# Interface.net
KiCad netlist of a schematic drawn in Altium Designer
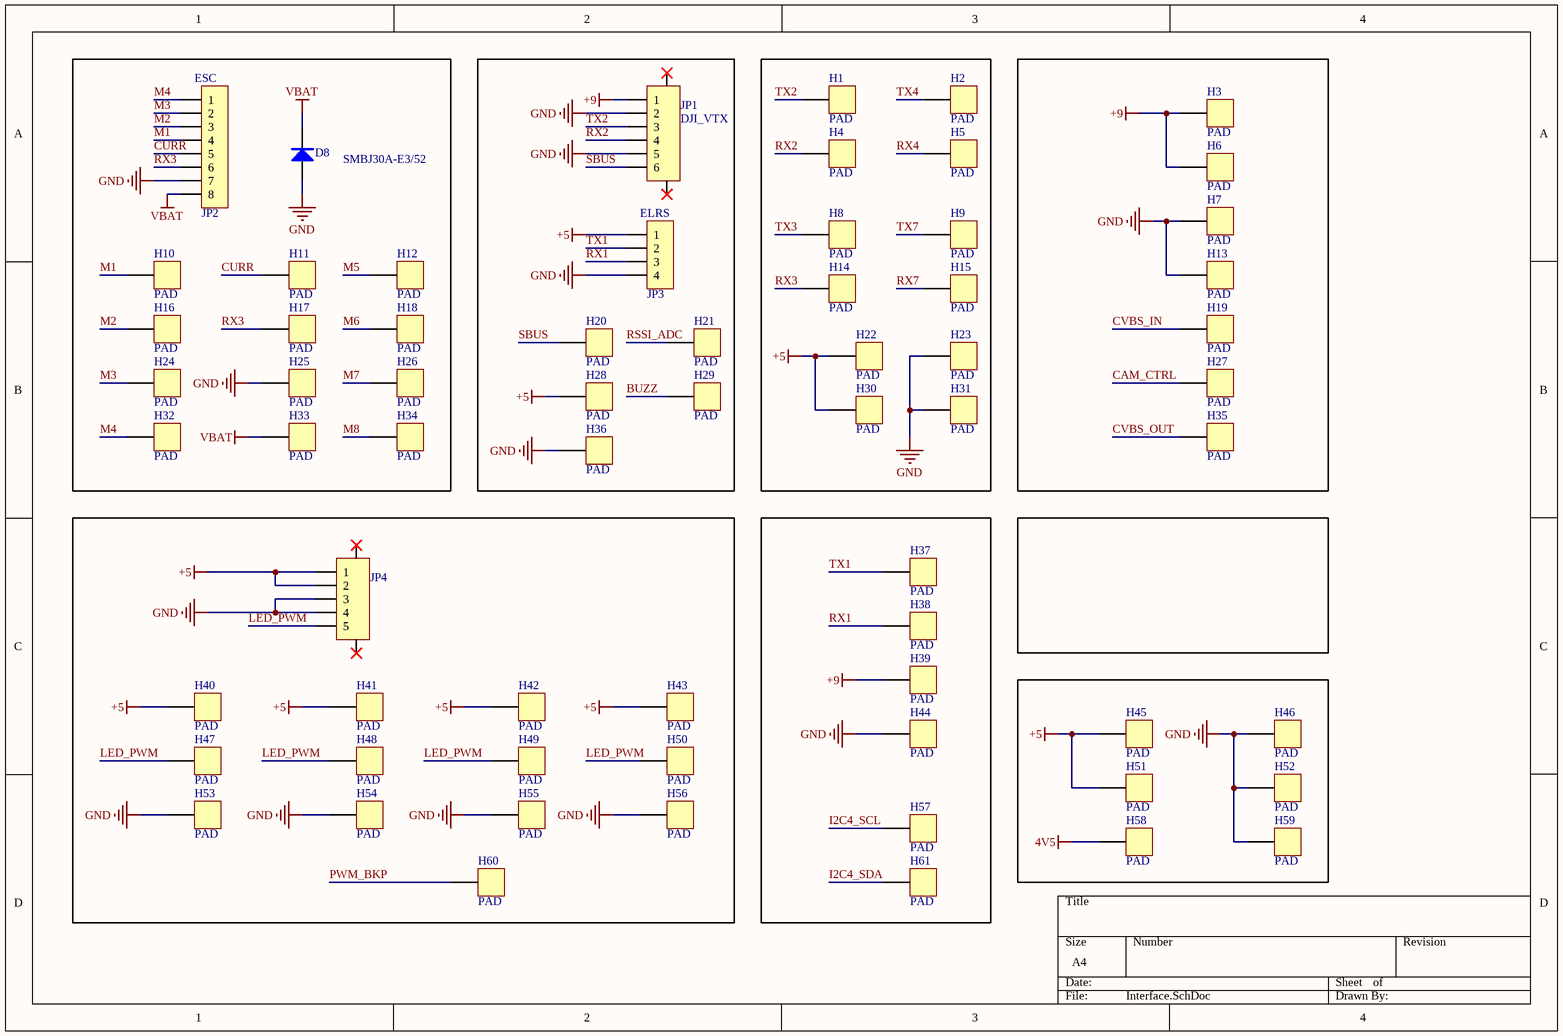
[diagram p0: Interface.SchDoc]

(export (version "E")
  (design (tool "Eeschema 10.0.6"))
  (components
    (comp (ref "D8")
      (value "SMBJ30A-E3/52")
      (footprint "SMB")
      (description "30V 600W 瞬态抑制二极管(TVS)")
      (libsource (lib "AxisQuad Components Lib") (part "SMBJ30A-E3/52"))
    )
    (comp (ref "H1")
      (value "PAD")
      (footprint "Pad 4")
      (description "Pads")
      (libsource (lib "Daedalus Components Lib") (part "PAD"))
    )
    (comp (ref "H2")
      (value "PAD")
      (footprint "Pad 4")
      (description "Pads")
      (libsource (lib "Daedalus Components Lib") (part "PAD"))
    )
    (comp (ref "H3")
      (value "PAD")
      (footprint "Pad 4")
      (description "Pads")
      (libsource (lib "Daedalus Components Lib") (part "PAD"))
    )
    (comp (ref "H4")
      (value "PAD")
      (footprint "Pad 4")
      (description "Pads")
      (libsource (lib "Daedalus Components Lib") (part "PAD"))
    )
    (comp (ref "H5")
      (value "PAD")
      (footprint "Pad 4")
      (description "Pads")
      (libsource (lib "Daedalus Components Lib") (part "PAD"))
    )
    (comp (ref "H6")
      (value "PAD")
      (footprint "Pad 4")
      (description "Pads")
      (libsource (lib "Daedalus Components Lib") (part "PAD"))
    )
    (comp (ref "H7")
      (value "PAD")
      (footprint "Pad 4")
      (description "Pads")
      (libsource (lib "Daedalus Components Lib") (part "PAD"))
    )
    (comp (ref "H8")
      (value "PAD")
      (footprint "Pad 4")
      (description "Pads")
      (libsource (lib "Daedalus Components Lib") (part "PAD"))
    )
    (comp (ref "H9")
      (value "PAD")
      (footprint "Pad 4")
      (description "Pads")
      (libsource (lib "Daedalus Components Lib") (part "PAD"))
    )
    (comp (ref "H10")
      (value "PAD")
      (footprint "Pad 4")
      (description "Pads")
      (libsource (lib "Daedalus Components Lib") (part "PAD"))
    )
    (comp (ref "H11")
      (value "PAD")
      (footprint "Pad 4")
      (description "Pads")
      (libsource (lib "Daedalus Components Lib") (part "PAD"))
    )
    (comp (ref "H12")
      (value "PAD")
      (footprint "Pad 4")
      (description "Pads")
      (libsource (lib "Daedalus Components Lib") (part "PAD"))
    )
    (comp (ref "H13")
      (value "PAD")
      (footprint "Pad 4")
      (description "Pads")
      (libsource (lib "Daedalus Components Lib") (part "PAD"))
    )
    (comp (ref "H14")
      (value "PAD")
      (footprint "Pad 4")
      (description "Pads")
      (libsource (lib "Daedalus Components Lib") (part "PAD"))
    )
    (comp (ref "H15")
      (value "PAD")
      (footprint "Pad 4")
      (description "Pads")
      (libsource (lib "Daedalus Components Lib") (part "PAD"))
    )
    (comp (ref "H16")
      (value "PAD")
      (footprint "Pad 4")
      (description "Pads")
      (libsource (lib "Daedalus Components Lib") (part "PAD"))
    )
    (comp (ref "H17")
      (value "PAD")
      (footprint "Pad 4")
      (description "Pads")
      (libsource (lib "Daedalus Components Lib") (part "PAD"))
    )
    (comp (ref "H18")
      (value "PAD")
      (footprint "Pad 4")
      (description "Pads")
      (libsource (lib "Daedalus Components Lib") (part "PAD"))
    )
    (comp (ref "H19")
      (value "PAD")
      (footprint "Pad 4")
      (description "Pads")
      (libsource (lib "Daedalus Components Lib") (part "PAD"))
    )
    (comp (ref "H20")
      (value "PAD")
      (footprint "Pad 4")
      (description "Pads")
      (libsource (lib "Daedalus Components Lib") (part "PAD"))
    )
    (comp (ref "H21")
      (value "PAD")
      (footprint "Pad 4")
      (description "Pads")
      (libsource (lib "Daedalus Components Lib") (part "PAD"))
    )
    (comp (ref "H22")
      (value "PAD")
      (footprint "Pad 4")
      (description "Pads")
      (libsource (lib "Daedalus Components Lib") (part "PAD"))
    )
    (comp (ref "H23")
      (value "PAD")
      (footprint "Pad 4")
      (description "Pads")
      (libsource (lib "Daedalus Components Lib") (part "PAD"))
    )
    (comp (ref "H24")
      (value "PAD")
      (footprint "Pad 4")
      (description "Pads")
      (libsource (lib "Daedalus Components Lib") (part "PAD"))
    )
    (comp (ref "H25")
      (value "PAD")
      (footprint "Pad 4")
      (description "Pads")
      (libsource (lib "Daedalus Components Lib") (part "PAD"))
    )
    (comp (ref "H26")
      (value "PAD")
      (footprint "Pad 4")
      (description "Pads")
      (libsource (lib "Daedalus Components Lib") (part "PAD"))
    )
    (comp (ref "H27")
      (value "PAD")
      (footprint "Pad 4")
      (description "Pads")
      (libsource (lib "Daedalus Components Lib") (part "PAD"))
    )
    (comp (ref "H28")
      (value "PAD")
      (footprint "Pad 4")
      (description "Pads")
      (libsource (lib "Daedalus Components Lib") (part "PAD"))
    )
    (comp (ref "H29")
      (value "PAD")
      (footprint "Pad 4")
      (description "Pads")
      (libsource (lib "Daedalus Components Lib") (part "PAD"))
    )
    (comp (ref "H30")
      (value "PAD")
      (footprint "Pad 4")
      (description "Pads")
      (libsource (lib "Daedalus Components Lib") (part "PAD"))
    )
    (comp (ref "H31")
      (value "PAD")
      (footprint "Pad 4")
      (description "Pads")
      (libsource (lib "Daedalus Components Lib") (part "PAD"))
    )
    (comp (ref "H32")
      (value "PAD")
      (footprint "Pad 4")
      (description "Pads")
      (libsource (lib "Daedalus Components Lib") (part "PAD"))
    )
    (comp (ref "H33")
      (value "PAD")
      (footprint "Pad 4")
      (description "Pads")
      (libsource (lib "Daedalus Components Lib") (part "PAD"))
    )
    (comp (ref "H34")
      (value "PAD")
      (footprint "Pad 4")
      (description "Pads")
      (libsource (lib "Daedalus Components Lib") (part "PAD"))
    )
    (comp (ref "H35")
      (value "PAD")
      (footprint "Pad 4")
      (description "Pads")
      (libsource (lib "Daedalus Components Lib") (part "PAD"))
    )
    (comp (ref "H36")
      (value "PAD")
      (footprint "Pad 4")
      (description "Pads")
      (libsource (lib "Daedalus Components Lib") (part "PAD"))
    )
    (comp (ref "H37")
      (value "PAD")
      (footprint "Pad 4")
      (description "Pads")
      (libsource (lib "Daedalus Components Lib") (part "PAD"))
    )
    (comp (ref "H38")
      (value "PAD")
      (footprint "Pad 4")
      (description "Pads")
      (libsource (lib "Daedalus Components Lib") (part "PAD"))
    )
    (comp (ref "H39")
      (value "PAD")
      (footprint "Pad 4")
      (description "Pads")
      (libsource (lib "Daedalus Components Lib") (part "PAD"))
    )
    (comp (ref "H40")
      (value "PAD")
      (footprint "Pad 2")
      (description "Pads")
      (libsource (lib "Daedalus Components Lib") (part "PAD"))
    )
    (comp (ref "H41")
      (value "PAD")
      (footprint "Pad 2")
      (description "Pads")
      (libsource (lib "Daedalus Components Lib") (part "PAD"))
    )
    (comp (ref "H42")
      (value "PAD")
      (footprint "Pad 2")
      (description "Pads")
      (libsource (lib "Daedalus Components Lib") (part "PAD"))
    )
    (comp (ref "H43")
      (value "PAD")
      (footprint "Pad 2")
      (description "Pads")
      (libsource (lib "Daedalus Components Lib") (part "PAD"))
    )
    (comp (ref "H44")
      (value "PAD")
      (footprint "Pad 4")
      (description "Pads")
      (libsource (lib "Daedalus Components Lib") (part "PAD"))
    )
    (comp (ref "H45")
      (value "PAD")
      (footprint "Pad 4")
      (description "Pads")
      (libsource (lib "Daedalus Components Lib") (part "PAD"))
    )
    (comp (ref "H46")
      (value "PAD")
      (footprint "Pad 4")
      (description "Pads")
      (libsource (lib "Daedalus Components Lib") (part "PAD"))
    )
    (comp (ref "H47")
      (value "PAD")
      (footprint "Pad 2")
      (description "Pads")
      (libsource (lib "Daedalus Components Lib") (part "PAD"))
    )
    (comp (ref "H48")
      (value "PAD")
      (footprint "Pad 2")
      (description "Pads")
      (libsource (lib "Daedalus Components Lib") (part "PAD"))
    )
    (comp (ref "H49")
      (value "PAD")
      (footprint "Pad 2")
      (description "Pads")
      (libsource (lib "Daedalus Components Lib") (part "PAD"))
    )
    (comp (ref "H50")
      (value "PAD")
      (footprint "Pad 2")
      (description "Pads")
      (libsource (lib "Daedalus Components Lib") (part "PAD"))
    )
    (comp (ref "H51")
      (value "PAD")
      (footprint "Pad 4")
      (description "Pads")
      (libsource (lib "Daedalus Components Lib") (part "PAD"))
    )
    (comp (ref "H52")
      (value "PAD")
      (footprint "Pad 4")
      (description "Pads")
      (libsource (lib "Daedalus Components Lib") (part "PAD"))
    )
    (comp (ref "H53")
      (value "PAD")
      (footprint "Pad 2")
      (description "Pads")
      (libsource (lib "Daedalus Components Lib") (part "PAD"))
    )
    (comp (ref "H54")
      (value "PAD")
      (footprint "Pad 2")
      (description "Pads")
      (libsource (lib "Daedalus Components Lib") (part "PAD"))
    )
    (comp (ref "H55")
      (value "PAD")
      (footprint "Pad 2")
      (description "Pads")
      (libsource (lib "Daedalus Components Lib") (part "PAD"))
    )
    (comp (ref "H56")
      (value "PAD")
      (footprint "Pad 2")
      (description "Pads")
      (libsource (lib "Daedalus Components Lib") (part "PAD"))
    )
    (comp (ref "H57")
      (value "PAD")
      (footprint "Pad 4")
      (description "Pads")
      (libsource (lib "Daedalus Components Lib") (part "PAD"))
    )
    (comp (ref "H58")
      (value "PAD")
      (footprint "Pad 2")
      (description "Pads")
      (libsource (lib "Daedalus Components Lib") (part "PAD"))
    )
    (comp (ref "H59")
      (value "PAD")
      (footprint "Pad 2")
      (description "Pads")
      (libsource (lib "Daedalus Components Lib") (part "PAD"))
    )
    (comp (ref "H60")
      (value "PAD")
      (footprint "Pad 2")
      (description "Pads")
      (libsource (lib "Daedalus Components Lib") (part "PAD"))
    )
    (comp (ref "H61")
      (value "PAD")
      (footprint "Pad 4")
      (description "Pads")
      (libsource (lib "Daedalus Components Lib") (part "PAD"))
    )
    (comp (ref "JP1")
      (value "CON-6P")
      (footprint "SH1.0-WT-6P")
      (description "6P连接器")
      (libsource (lib "AxisQuad Components Lib") (part "Header 6"))
    )
    (comp (ref "JP2")
      (value "CON-8P")
      (footprint "SH1.0-WT-8P")
      (description "8P连接器")
      (libsource (lib "AxisQuad Components Lib") (part "Header 8"))
    )
    (comp (ref "JP3")
      (value "CON-4P")
      (footprint "SH1.0-WT-4P")
      (description "4P连接器")
      (libsource (lib "AxisQuad Components Lib") (part "Header 4"))
    )
    (comp (ref "JP4")
      (value "CON-5P")
      (footprint "SH1.0-WT-5P")
      (description "5P连接器")
      (libsource (lib "AxisQuad Components Lib") (part "Header 5"))
    )
  )
  (nets
    (net (code "1") (name "+5") (class "Default")
      (node (ref "H22") (pin "1") (pinfunction "1_1") (pintype "passive"))
      (node (ref "H28") (pin "1") (pinfunction "1_1") (pintype "passive"))
      (node (ref "H30") (pin "1") (pinfunction "1_1") (pintype "passive"))
      (node (ref "H40") (pin "1") (pinfunction "1_1") (pintype "passive"))
      (node (ref "H41") (pin "1") (pinfunction "1_1") (pintype "passive"))
      (node (ref "H42") (pin "1") (pinfunction "1_1") (pintype "passive"))
      (node (ref "H43") (pin "1") (pinfunction "1_1") (pintype "passive"))
      (node (ref "H45") (pin "1") (pinfunction "1_1") (pintype "passive"))
      (node (ref "H51") (pin "1") (pinfunction "1_1") (pintype "passive"))
      (node (ref "JP3") (pin "1") (pinfunction "1_1") (pintype "passive"))
      (node (ref "JP4") (pin "1") (pinfunction "1_1") (pintype "passive"))
      (node (ref "JP4") (pin "2") (pinfunction "2_2") (pintype "passive"))
    )
    (net (code "2") (name "+9") (class "Default")
      (node (ref "H3") (pin "1") (pinfunction "1_1") (pintype "passive"))
      (node (ref "H39") (pin "1") (pinfunction "1_1") (pintype "passive"))
      (node (ref "H6") (pin "1") (pinfunction "1_1") (pintype "passive"))
      (node (ref "JP1") (pin "1") (pinfunction "1_1") (pintype "passive"))
    )
    (net (code "3") (name "/BUZZ") (class "Default")
      (node (ref "H29") (pin "1") (pinfunction "1_1") (pintype "passive"))
    )
    (net (code "4") (name "/CAM_CTRL") (class "Default")
      (node (ref "H27") (pin "1") (pinfunction "1_1") (pintype "passive"))
    )
    (net (code "5") (name "/CURR") (class "Default")
      (node (ref "H11") (pin "1") (pinfunction "1_1") (pintype "passive"))
      (node (ref "JP2") (pin "5") (pinfunction "5_5") (pintype "passive"))
    )
    (net (code "6") (name "/CVBS_IN") (class "Default")
      (node (ref "H19") (pin "1") (pinfunction "1_1") (pintype "passive"))
    )
    (net (code "7") (name "/CVBS_OUT") (class "Default")
      (node (ref "H35") (pin "1") (pinfunction "1_1") (pintype "passive"))
    )
    (net (code "8") (name "/I2C4_SCL") (class "Default")
      (node (ref "H57") (pin "1") (pinfunction "1_1") (pintype "passive"))
    )
    (net (code "9") (name "/I2C4_SDA") (class "Default")
      (node (ref "H61") (pin "1") (pinfunction "1_1") (pintype "passive"))
    )
    (net (code "10") (name "/LED_PWM") (class "Default")
      (node (ref "H47") (pin "1") (pinfunction "1_1") (pintype "passive"))
      (node (ref "H48") (pin "1") (pinfunction "1_1") (pintype "passive"))
      (node (ref "H49") (pin "1") (pinfunction "1_1") (pintype "passive"))
      (node (ref "H50") (pin "1") (pinfunction "1_1") (pintype "passive"))
      (node (ref "JP4") (pin "5") (pinfunction "5_5") (pintype "passive"))
    )
    (net (code "11") (name "/M1") (class "Default")
      (node (ref "H10") (pin "1") (pinfunction "1_1") (pintype "passive"))
      (node (ref "JP2") (pin "4") (pinfunction "4_4") (pintype "passive"))
    )
    (net (code "12") (name "/M2") (class "Default")
      (node (ref "H16") (pin "1") (pinfunction "1_1") (pintype "passive"))
      (node (ref "JP2") (pin "3") (pinfunction "3_3") (pintype "passive"))
    )
    (net (code "13") (name "/M3") (class "Default")
      (node (ref "H24") (pin "1") (pinfunction "1_1") (pintype "passive"))
      (node (ref "JP2") (pin "2") (pinfunction "2_2") (pintype "passive"))
    )
    (net (code "14") (name "/M4") (class "Default")
      (node (ref "H32") (pin "1") (pinfunction "1_1") (pintype "passive"))
      (node (ref "JP2") (pin "1") (pinfunction "1_1") (pintype "passive"))
    )
    (net (code "15") (name "/M5") (class "Default")
      (node (ref "H12") (pin "1") (pinfunction "1_1") (pintype "passive"))
    )
    (net (code "16") (name "/M6") (class "Default")
      (node (ref "H18") (pin "1") (pinfunction "1_1") (pintype "passive"))
    )
    (net (code "17") (name "/M7") (class "Default")
      (node (ref "H26") (pin "1") (pinfunction "1_1") (pintype "passive"))
    )
    (net (code "18") (name "/M8") (class "Default")
      (node (ref "H34") (pin "1") (pinfunction "1_1") (pintype "passive"))
    )
    (net (code "19") (name "/PWM_BKP") (class "Default")
      (node (ref "H60") (pin "1") (pinfunction "1_1") (pintype "passive"))
    )
    (net (code "20") (name "/RSSI_ADC") (class "Default")
      (node (ref "H21") (pin "1") (pinfunction "1_1") (pintype "passive"))
    )
    (net (code "21") (name "/RX1") (class "Default")
      (node (ref "H38") (pin "1") (pinfunction "1_1") (pintype "passive"))
      (node (ref "JP3") (pin "3") (pinfunction "3_3") (pintype "passive"))
    )
    (net (code "22") (name "/RX2") (class "Default")
      (node (ref "H4") (pin "1") (pinfunction "1_1") (pintype "passive"))
      (node (ref "JP1") (pin "4") (pinfunction "4_4") (pintype "passive"))
    )
    (net (code "23") (name "/RX3") (class "Default")
      (node (ref "H14") (pin "1") (pinfunction "1_1") (pintype "passive"))
      (node (ref "H17") (pin "1") (pinfunction "1_1") (pintype "passive"))
      (node (ref "JP2") (pin "6") (pinfunction "6_6") (pintype "passive"))
    )
    (net (code "24") (name "/RX4") (class "Default")
      (node (ref "H5") (pin "1") (pinfunction "1_1") (pintype "passive"))
    )
    (net (code "25") (name "/RX7") (class "Default")
      (node (ref "H15") (pin "1") (pinfunction "1_1") (pintype "passive"))
    )
    (net (code "26") (name "/SBUS") (class "Default")
      (node (ref "H20") (pin "1") (pinfunction "1_1") (pintype "passive"))
      (node (ref "JP1") (pin "6") (pinfunction "6_6") (pintype "passive"))
    )
    (net (code "27") (name "/TX1") (class "Default")
      (node (ref "H37") (pin "1") (pinfunction "1_1") (pintype "passive"))
      (node (ref "JP3") (pin "2") (pinfunction "2_2") (pintype "passive"))
    )
    (net (code "28") (name "/TX2") (class "Default")
      (node (ref "H1") (pin "1") (pinfunction "1_1") (pintype "passive"))
      (node (ref "JP1") (pin "3") (pinfunction "3_3") (pintype "passive"))
    )
    (net (code "29") (name "/TX3") (class "Default")
      (node (ref "H8") (pin "1") (pinfunction "1_1") (pintype "passive"))
    )
    (net (code "30") (name "/TX4") (class "Default")
      (node (ref "H2") (pin "1") (pinfunction "1_1") (pintype "passive"))
    )
    (net (code "31") (name "/TX7") (class "Default")
      (node (ref "H9") (pin "1") (pinfunction "1_1") (pintype "passive"))
    )
    (net (code "32") (name "4V5") (class "Default")
      (node (ref "H58") (pin "1") (pinfunction "1_1") (pintype "passive"))
    )
    (net (code "33") (name "GND") (class "Default")
      (node (ref "D8") (pin "1") (pinfunction "A_1") (pintype "passive"))
      (node (ref "H13") (pin "1") (pinfunction "1_1") (pintype "passive"))
      (node (ref "H23") (pin "1") (pinfunction "1_1") (pintype "passive"))
      (node (ref "H25") (pin "1") (pinfunction "1_1") (pintype "passive"))
      (node (ref "H31") (pin "1") (pinfunction "1_1") (pintype "passive"))
      (node (ref "H36") (pin "1") (pinfunction "1_1") (pintype "passive"))
      (node (ref "H44") (pin "1") (pinfunction "1_1") (pintype "passive"))
      (node (ref "H46") (pin "1") (pinfunction "1_1") (pintype "passive"))
      (node (ref "H52") (pin "1") (pinfunction "1_1") (pintype "passive"))
      (node (ref "H53") (pin "1") (pinfunction "1_1") (pintype "passive"))
      (node (ref "H54") (pin "1") (pinfunction "1_1") (pintype "passive"))
      (node (ref "H55") (pin "1") (pinfunction "1_1") (pintype "passive"))
      (node (ref "H56") (pin "1") (pinfunction "1_1") (pintype "passive"))
      (node (ref "H59") (pin "1") (pinfunction "1_1") (pintype "passive"))
      (node (ref "H7") (pin "1") (pinfunction "1_1") (pintype "passive"))
      (node (ref "JP1") (pin "2") (pinfunction "2_2") (pintype "passive"))
      (node (ref "JP1") (pin "5") (pinfunction "5_5") (pintype "passive"))
      (node (ref "JP2") (pin "7") (pinfunction "7_7") (pintype "passive"))
      (node (ref "JP3") (pin "4") (pinfunction "4_4") (pintype "passive"))
      (node (ref "JP4") (pin "3") (pinfunction "3_3") (pintype "passive"))
      (node (ref "JP4") (pin "4") (pinfunction "4_4") (pintype "passive"))
    )
    (net (code "34") (name "VBAT") (class "Default")
      (node (ref "D8") (pin "2") (pinfunction "K_2") (pintype "passive"))
      (node (ref "H33") (pin "1") (pinfunction "1_1") (pintype "passive"))
      (node (ref "JP2") (pin "8") (pinfunction "8_8") (pintype "passive"))
    )
    (net (code "35") (name "unconnected-(JP1-Pad0)") (class "Default")
      (node (ref "JP1") (pin "0") (pinfunction "0_0") (pintype "passive+no_connect"))
    )
    (net (code "36") (name "unconnected-(JP1-Pad0)_1") (class "Default")
      (node (ref "JP1") (pin "0") (pinfunction "0_0") (pintype "passive+no_connect"))
    )
    (net (code "37") (name "unconnected-(JP4-Pad0)") (class "Default")
      (node (ref "JP4") (pin "0") (pinfunction "0_0") (pintype "passive+no_connect"))
    )
    (net (code "38") (name "unconnected-(JP4-Pad0)_1") (class "Default")
      (node (ref "JP4") (pin "0") (pinfunction "0_0") (pintype "passive+no_connect"))
    )
  )
)
